# capelet_storage.net
KiCad netlist of a schematic drawn in EAGLE
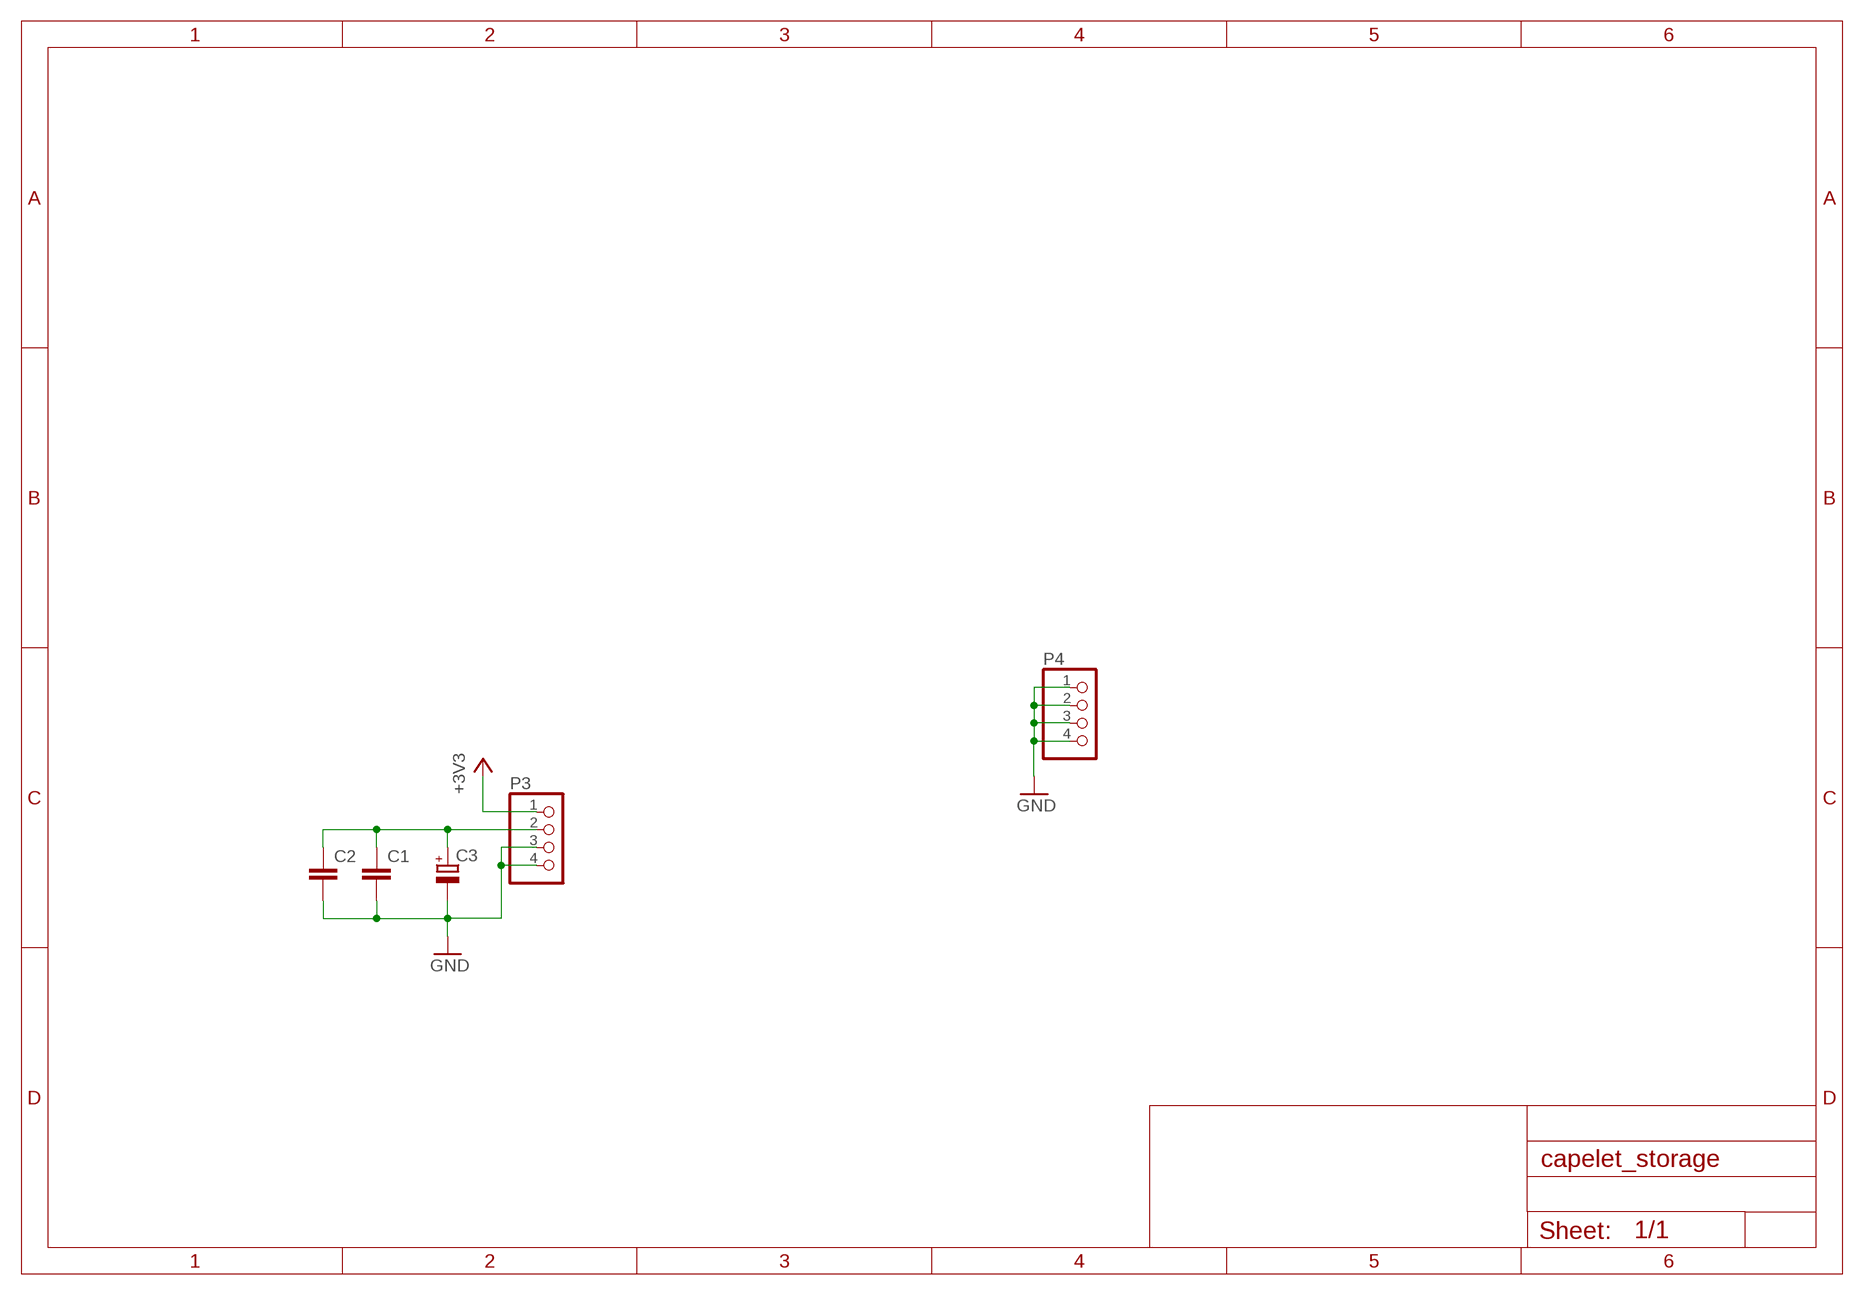
[diagram p0: schematic, sheet 1]

(export (version "E")
  (design (tool "Eeschema 10.0.6"))
  (components
    (comp (ref "C1")
      (value "C_SMD0805")
      (footprint "eagle-import:CAPC2012X145")
      (libsource (lib "eagle-import") (part "C_SMD0805"))
    )
    (comp (ref "C2")
      (value "C_SMD1210")
      (footprint "eagle-import:CAPC3225X280")
      (libsource (lib "eagle-import") (part "C_SMD1210"))
    )
    (comp (ref "C3")
      (value "CPOL-EUE5-8.5")
      (footprint "eagle-import:E5-8,5")
      (libsource (lib "eagle-import") (part "CPOL-EUE5-8.5"))
    )
    (comp (ref "P3")
      (value "PINHD-1X4")
      (footprint "eagle-import:1X04")
      (libsource (lib "eagle-import") (part "PINHD-1X4"))
    )
    (comp (ref "P4")
      (value "PINHD-1X4")
      (footprint "eagle-import:1X04")
      (libsource (lib "eagle-import") (part "PINHD-1X4"))
    )
  )
  (nets
    (net (code "1") (name "+3V3") (class "Default")
      (node (ref "P3") (pin "1") (pinfunction "1_1") (pintype "passive"))
    )
    (net (code "2") (name "GND") (class "Default")
      (node (ref "C1") (pin "2") (pinfunction "2_2") (pintype "passive"))
      (node (ref "C2") (pin "2") (pinfunction "2_2") (pintype "passive"))
      (node (ref "C3") (pin "-") (pinfunction "-_-") (pintype "passive"))
      (node (ref "P3") (pin "3") (pinfunction "3_3") (pintype "passive"))
      (node (ref "P3") (pin "4") (pinfunction "4_4") (pintype "passive"))
      (node (ref "P4") (pin "1") (pinfunction "1_1") (pintype "passive"))
      (node (ref "P4") (pin "2") (pinfunction "2_2") (pintype "passive"))
      (node (ref "P4") (pin "3") (pinfunction "3_3") (pintype "passive"))
      (node (ref "P4") (pin "4") (pinfunction "4_4") (pintype "passive"))
    )
    (net (code "3") (name "Net-(C1-Pad1)") (class "Default")
      (node (ref "C1") (pin "1") (pinfunction "1_1") (pintype "passive"))
      (node (ref "C2") (pin "1") (pinfunction "1_1") (pintype "passive"))
      (node (ref "C3") (pin "+") (pinfunction "+_+") (pintype "passive"))
      (node (ref "P3") (pin "2") (pinfunction "2_2") (pintype "passive"))
    )
  )
)
